# led_phototransistor.net
KiCad netlist of a schematic drawn in Altium Designer
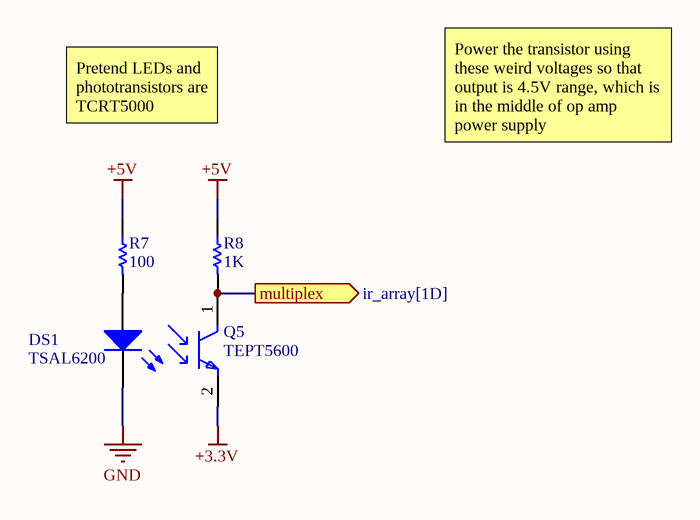
[diagram p0: led_phototransistor.SchDoc]

(export (version "E")
  (design (tool "Eeschema 10.0.6"))
  (components
    (comp (ref "DS1")
      (value "TSAL6200")
      (footprint "VISH-TSAL6200")
      (fields (field (name "MANUFACTURER") "Vishay"))
      (libsource (lib "Altium Content Vault") (part "LED-AK-2"))
    )
    (comp (ref "Q5")
      (value "TEPT5600")
      (footprint "FP-6_544-5185_03-4-MFG")
      (description "SENSOR PHOTO 570NM TOP VIEW RAD")
      (libsource (lib "Altium Content Vault") (part "9456f77f46cf90b3cfae45295d5ca59"))
    )
    (comp (ref "R7")
      (value "100")
      (description "Resistor")
      (libsource (lib "Simulation Generic Components") (part "Resistor"))
    )
    (comp (ref "R8")
      (value "1K")
      (description "Resistor")
      (libsource (lib "Simulation Generic Components") (part "Resistor"))
    )
  )
  (nets
    (net (code "1") (name "+3.3V") (class "Default")
      (node (ref "Q5") (pin "2") (pinfunction "E_2") (pintype "passive"))
    )
    (net (code "2") (name "+5V") (class "Default")
      (node (ref "R7") (pin "1") (pinfunction "1_1") (pintype "passive"))
      (node (ref "R8") (pin "1") (pinfunction "1_1") (pintype "passive"))
    )
    (net (code "3") (name "/multiplex") (class "Default")
      (node (ref "Q5") (pin "1") (pinfunction "C_1") (pintype "passive"))
      (node (ref "R8") (pin "2") (pinfunction "2_2") (pintype "passive"))
    )
    (net (code "4") (name "GND") (class "Default")
      (node (ref "DS1") (pin "2") (pinfunction "K_2") (pintype "passive"))
    )
    (net (code "5") (name "Net-(DS1-A)") (class "Default")
      (node (ref "DS1") (pin "1") (pinfunction "A_1") (pintype "passive"))
      (node (ref "R7") (pin "2") (pinfunction "2_2") (pintype "passive"))
    )
  )
)
